# templog3.net
KiCad netlist of a schematic drawn in EAGLE
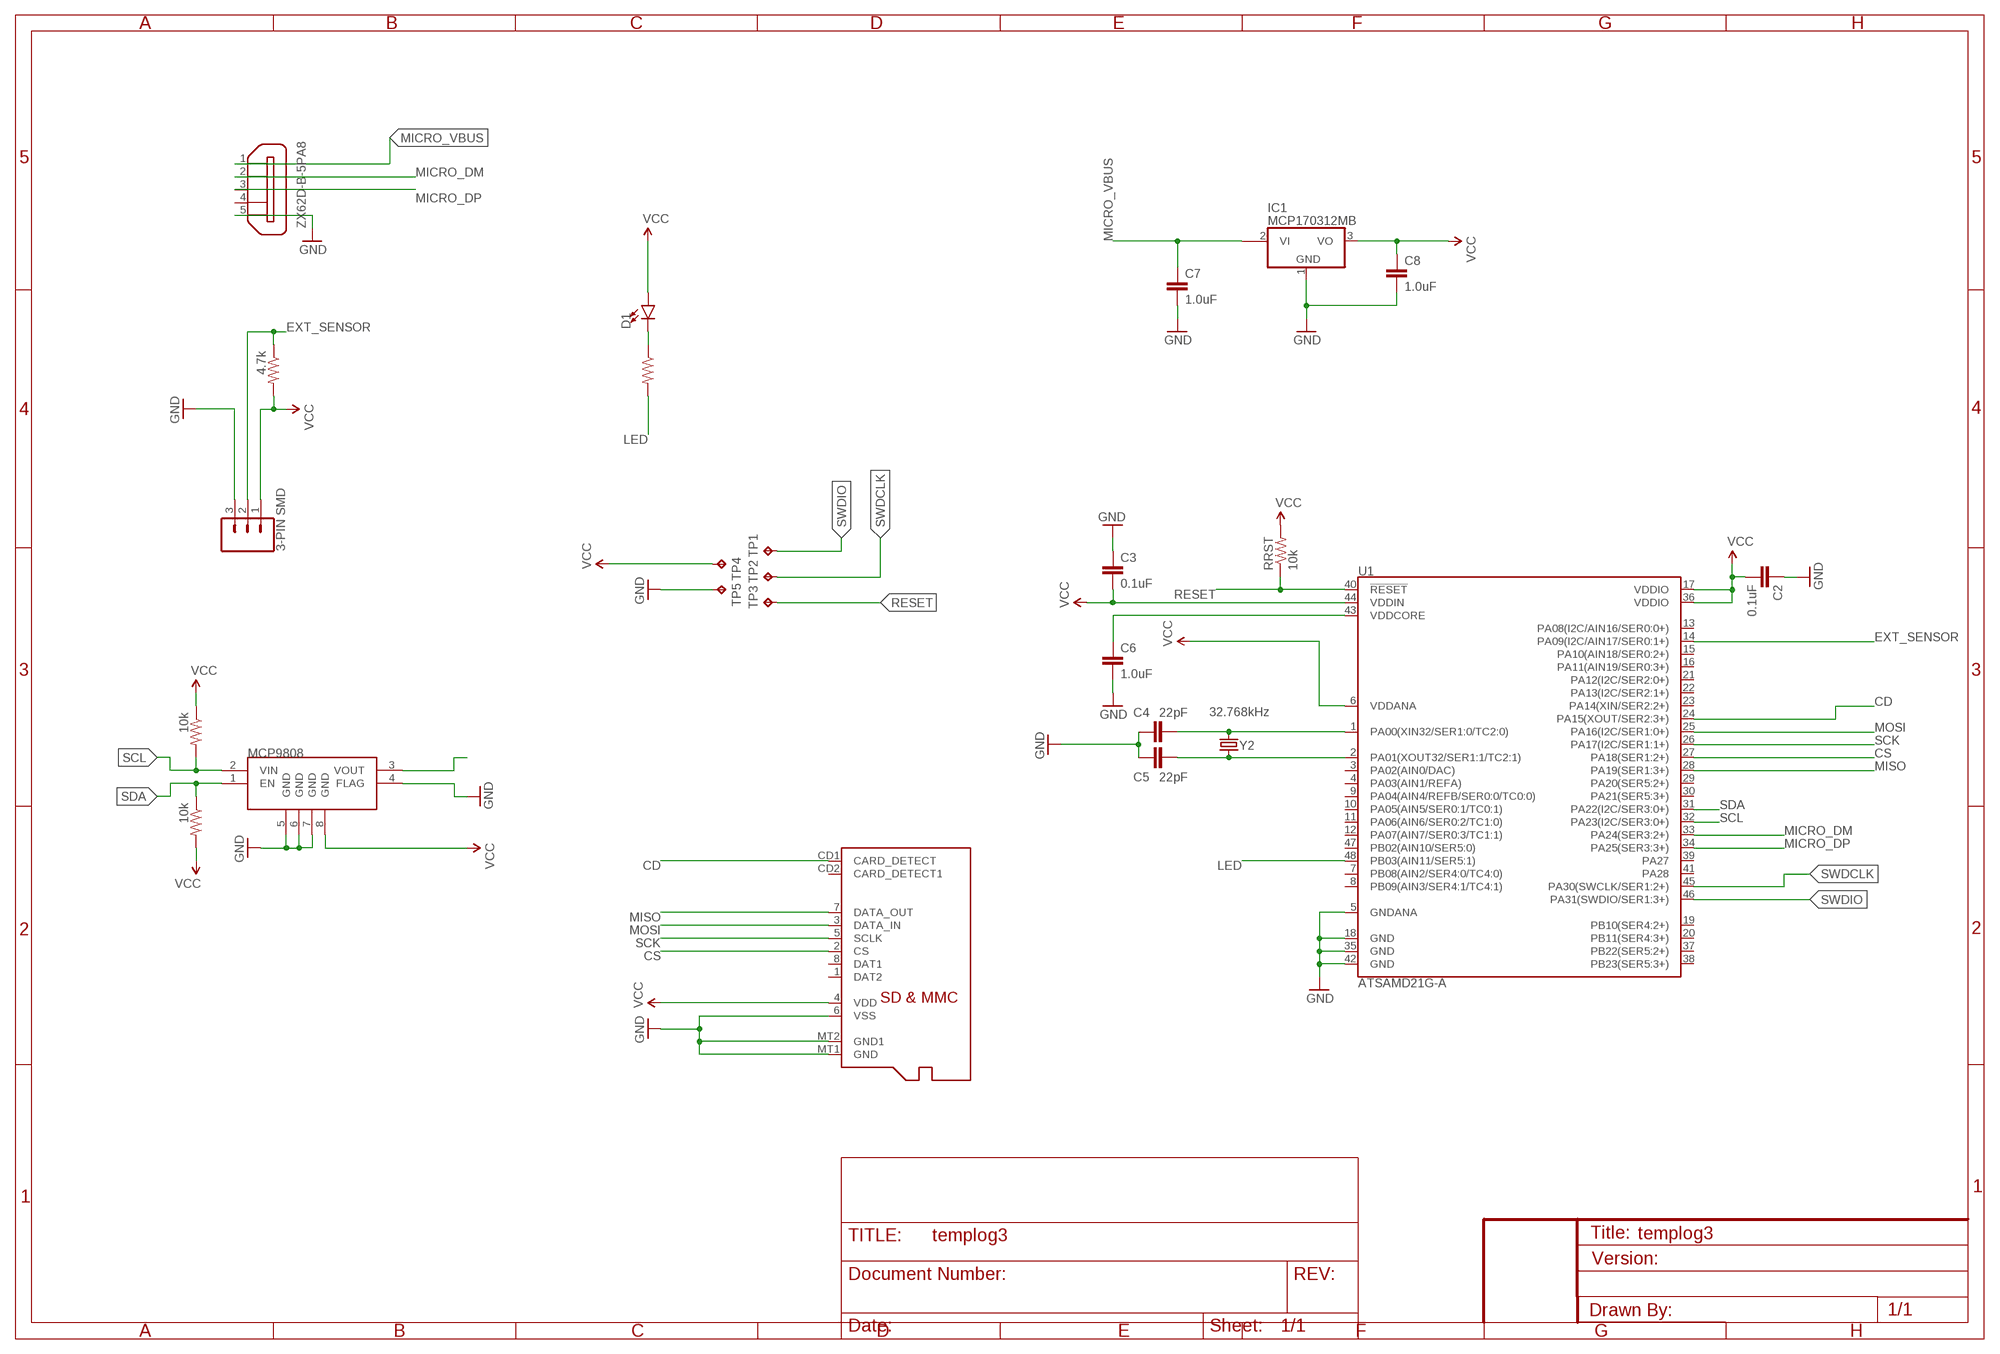
[diagram p0: schematic, sheet 1]

(export (version "E")
  (design (tool "Eeschema 10.0.6"))
  (components
    (comp (ref "C2")
      (value "0.1uF")
      (footprint "eagle-import:0805")
      (libsource (lib "eagle-import") (part "1.0UF-0805-25V-10%"))
    )
    (comp (ref "C3")
      (value "0.1uF")
      (footprint "eagle-import:0805")
      (libsource (lib "eagle-import") (part "1.0UF-0805-25V-10%"))
    )
    (comp (ref "C4")
      (value "22pF")
      (footprint "eagle-import:0805")
      (libsource (lib "eagle-import") (part "CAP0805"))
    )
    (comp (ref "C5")
      (value "22pF")
      (footprint "eagle-import:0805")
      (libsource (lib "eagle-import") (part "CAP0805"))
    )
    (comp (ref "C6")
      (value "1.0uF")
      (footprint "eagle-import:0805")
      (libsource (lib "eagle-import") (part "1.0UF-0805-25V-10%"))
    )
    (comp (ref "C7")
      (value "1.0uF")
      (footprint "eagle-import:0805")
      (libsource (lib "eagle-import") (part "1.0UF-0805-25V-10%"))
    )
    (comp (ref "C8")
      (value "1.0uF")
      (footprint "eagle-import:0805")
      (libsource (lib "eagle-import") (part "1.0UF-0805-25V-10%"))
    )
    (comp (ref "D1")
      (value "LED1206")
      (footprint "eagle-import:LED-1206")
      (libsource (lib "eagle-import") (part "LED1206"))
    )
    (comp (ref "IC1")
      (value "MCP170312MB")
      (footprint "eagle-import:SOT89")
      (libsource (lib "eagle-import") (part "MCP1703MB12"))
    )
    (comp (ref "J2")
      (value "3-PIN SMD")
      (footprint "eagle-import:JST-3-SMD")
      (libsource (lib "eagle-import") (part "CONN_03JST-SMD"))
    )
    (comp (ref "MCP9808")
      (value "V_REG_MIC5216")
      (footprint "eagle-import:MSOP8")
      (libsource (lib "eagle-import") (part "V_REG_MIC5216"))
    )
    (comp (ref "RRST")
      (value "10k")
      (footprint "eagle-import:0805")
      (libsource (lib "eagle-import") (part "RESISTOR0805-RES"))
    )
    (comp (ref "R_I2C_1")
      (value "10k")
      (footprint "eagle-import:0805")
      (libsource (lib "eagle-import") (part "RESISTOR0805-RES"))
    )
    (comp (ref "R_I2C_2")
      (value "10k")
      (footprint "eagle-import:0805")
      (libsource (lib "eagle-import") (part "RESISTOR0805-RES"))
    )
    (comp (ref "R_I2C_3")
      (value "4.7k")
      (footprint "eagle-import:0805")
      (libsource (lib "eagle-import") (part "RESISTOR0805-RES"))
    )
    (comp (ref "R_I2C_4")
      (value "RESISTOR0805-RES")
      (footprint "eagle-import:0805")
      (libsource (lib "eagle-import") (part "RESISTOR0805-RES"))
    )
    (comp (ref "TP1")
      (value "TPB1,27")
      (footprint "eagle-import:B1,27")
      (libsource (lib "eagle-import") (part "TPB1,27"))
    )
    (comp (ref "TP2")
      (value "TPB1,27")
      (footprint "eagle-import:B1,27")
      (libsource (lib "eagle-import") (part "TPB1,27"))
    )
    (comp (ref "TP3")
      (value "TPB1,27")
      (footprint "eagle-import:B1,27")
      (libsource (lib "eagle-import") (part "TPB1,27"))
    )
    (comp (ref "TP4")
      (value "TPB1,27")
      (footprint "eagle-import:B1,27")
      (libsource (lib "eagle-import") (part "TPB1,27"))
    )
    (comp (ref "TP5")
      (value "TPB1,27")
      (footprint "eagle-import:B1,27")
      (libsource (lib "eagle-import") (part "TPB1,27"))
    )
    (comp (ref "U$1")
      (value "MICROSD")
      (footprint "eagle-import:MICROSD")
      (libsource (lib "eagle-import") (part "MICROSD"))
    )
    (comp (ref "U1")
      (value "ATSAMD21G-A")
      (footprint "eagle-import:TQFP-48")
      (libsource (lib "eagle-import") (part "ATSAMD21G-A"))
    )
    (comp (ref "X2")
      (value "ZX62D-B-5PA8")
      (footprint "eagle-import:ZX62D-B-5PA8")
      (fields (field (name "MF") "Hirose"))
      (libsource (lib "eagle-import") (part "ZX62D-B-5PA8"))
    )
    (comp (ref "Y2")
      (value "32.768kHz")
      (footprint "eagle-import:CRYSTAL-SMD-3.2X1.5MM")
      (libsource (lib "eagle-import") (part "CRYSTAL3.2X1.5MM"))
    )
  )
  (nets
    (net (code "1") (name "/CD") (class "Default")
      (node (ref "U$1") (pin "CD1") (pinfunction "CARD_DETECT_CD1") (pintype "passive"))
      (node (ref "U1") (pin "24") (pinfunction "PA15(XOUT/SER2:3+)_24") (pintype "bidirectional"))
    )
    (net (code "2") (name "/CS") (class "Default")
      (node (ref "U$1") (pin "2") (pinfunction "CS_2") (pintype "input"))
      (node (ref "U1") (pin "27") (pinfunction "PA18(SER1:2+)_27") (pintype "bidirectional"))
    )
    (net (code "3") (name "/EXT_SENSOR") (class "Default")
      (node (ref "J2") (pin "2") (pinfunction "2_2") (pintype "passive"))
      (node (ref "R_I2C_3") (pin "1") (pinfunction "1_1") (pintype "passive"))
      (node (ref "U1") (pin "14") (pinfunction "PA09(I2C/AIN17/SER0:1+)_14") (pintype "bidirectional"))
    )
    (net (code "4") (name "/LED") (class "Default")
      (node (ref "R_I2C_4") (pin "2") (pinfunction "2_2") (pintype "passive"))
      (node (ref "U1") (pin "48") (pinfunction "PB03(AIN11/SER5:1)_48") (pintype "bidirectional"))
    )
    (net (code "5") (name "/MICRO_DM") (class "Default")
      (node (ref "U1") (pin "33") (pinfunction "PA24(SER3:2+)_33") (pintype "bidirectional"))
      (node (ref "X2") (pin "2") (pinfunction "2_2") (pintype "passive"))
    )
    (net (code "6") (name "/MICRO_DP") (class "Default")
      (node (ref "U1") (pin "34") (pinfunction "PA25(SER3:3+)_34") (pintype "bidirectional"))
      (node (ref "X2") (pin "3") (pinfunction "3_3") (pintype "passive"))
    )
    (net (code "7") (name "/MISO") (class "Default")
      (node (ref "U$1") (pin "7") (pinfunction "DATA_OUT_7") (pintype "output"))
      (node (ref "U1") (pin "28") (pinfunction "PA19(SER1:3+)_28") (pintype "bidirectional"))
    )
    (net (code "8") (name "/MOSI") (class "Default")
      (node (ref "U$1") (pin "3") (pinfunction "DATA_IN_3") (pintype "input"))
      (node (ref "U1") (pin "25") (pinfunction "PA16(I2C/SER1:0+)_25") (pintype "bidirectional"))
    )
    (net (code "9") (name "/SCK") (class "Default")
      (node (ref "U$1") (pin "5") (pinfunction "SCLK_5") (pintype "input"))
      (node (ref "U1") (pin "26") (pinfunction "PA17(I2C/SER1:1+)_26") (pintype "bidirectional"))
    )
    (net (code "10") (name "GND") (class "Default")
      (node (ref "C2") (pin "1") (pinfunction "1_1") (pintype "passive"))
      (node (ref "C3") (pin "1") (pinfunction "1_1") (pintype "passive"))
      (node (ref "C4") (pin "1") (pinfunction "1_1") (pintype "passive"))
      (node (ref "C5") (pin "1") (pinfunction "1_1") (pintype "passive"))
      (node (ref "C6") (pin "2") (pinfunction "2_2") (pintype "passive"))
      (node (ref "C7") (pin "2") (pinfunction "2_2") (pintype "passive"))
      (node (ref "C8") (pin "2") (pinfunction "2_2") (pintype "passive"))
      (node (ref "IC1") (pin "1") (pinfunction "GND_1") (pintype "passive"))
      (node (ref "J2") (pin "3") (pinfunction "3_3") (pintype "passive"))
      (node (ref "MCP9808") (pin "4") (pinfunction "FLAG_4") (pintype "bidirectional"))
      (node (ref "MCP9808") (pin "5") (pinfunction "GND_5") (pintype "bidirectional"))
      (node (ref "MCP9808") (pin "6") (pinfunction "GND_6") (pintype "bidirectional"))
      (node (ref "MCP9808") (pin "7") (pinfunction "GND_7") (pintype "bidirectional"))
      (node (ref "TP5") (pin "TP") (pinfunction "TP_TP") (pintype "input"))
      (node (ref "U$1") (pin "6") (pinfunction "VSS_6") (pintype "power_in"))
      (node (ref "U$1") (pin "MT1") (pinfunction "GND_MT1") (pintype "power_in"))
      (node (ref "U$1") (pin "MT2") (pinfunction "GND1_MT2") (pintype "power_in"))
      (node (ref "U1") (pin "18") (pinfunction "GND_18") (pintype "bidirectional"))
      (node (ref "U1") (pin "35") (pinfunction "GND_35") (pintype "bidirectional"))
      (node (ref "U1") (pin "42") (pinfunction "GND_42") (pintype "bidirectional"))
      (node (ref "U1") (pin "5") (pinfunction "GNDANA_5") (pintype "bidirectional"))
      (node (ref "X2") (pin "5") (pinfunction "5_5") (pintype "passive"))
    )
    (net (code "11") (name "MICRO_VBUS") (class "Default")
      (node (ref "C7") (pin "1") (pinfunction "1_1") (pintype "passive"))
      (node (ref "IC1") (pin "2@1") (pinfunction "VI1_2@1") (pintype "input"))
      (node (ref "X2") (pin "1") (pinfunction "1_1") (pintype "passive"))
    )
    (net (code "12") (name "Net-(D1-PadC)") (class "Default")
      (node (ref "D1") (pin "C") (pinfunction "C_C") (pintype "passive"))
      (node (ref "R_I2C_4") (pin "1") (pinfunction "1_1") (pintype "passive"))
    )
    (net (code "13") (name "Net-(U1-PA00(XIN32{slash}SER1:0{slash}TC2:0))") (class "Default")
      (node (ref "C4") (pin "2") (pinfunction "2_2") (pintype "passive"))
      (node (ref "U1") (pin "1") (pinfunction "PA00(XIN32/SER1:0/TC2:0)_1") (pintype "bidirectional"))
      (node (ref "Y2") (pin "P$2") (pinfunction "2_P$2") (pintype "passive"))
    )
    (net (code "14") (name "Net-(U1-PA01(XOUT32{slash}SER1:1{slash}TC2:1))") (class "Default")
      (node (ref "C5") (pin "2") (pinfunction "2_2") (pintype "passive"))
      (node (ref "U1") (pin "2") (pinfunction "PA01(XOUT32/SER1:1/TC2:1)_2") (pintype "bidirectional"))
      (node (ref "Y2") (pin "P$1") (pinfunction "1_P$1") (pintype "passive"))
    )
    (net (code "15") (name "Net-(U1-VDDCORE)") (class "Default")
      (node (ref "C6") (pin "1") (pinfunction "1_1") (pintype "passive"))
      (node (ref "U1") (pin "43") (pinfunction "VDDCORE_43") (pintype "bidirectional"))
    )
    (net (code "16") (name "RESET") (class "Default")
      (node (ref "RRST") (pin "1") (pinfunction "1_1") (pintype "passive"))
      (node (ref "TP3") (pin "TP") (pinfunction "TP_TP") (pintype "input"))
      (node (ref "U1") (pin "40") (pinfunction "~{RESET}_40") (pintype "bidirectional"))
    )
    (net (code "17") (name "SCL") (class "Default")
      (node (ref "MCP9808") (pin "2") (pinfunction "VIN_2") (pintype "bidirectional"))
      (node (ref "R_I2C_1") (pin "2") (pinfunction "2_2") (pintype "passive"))
      (node (ref "U1") (pin "32") (pinfunction "PA23(I2C/SER3:0+)_32") (pintype "bidirectional"))
    )
    (net (code "18") (name "SDA") (class "Default")
      (node (ref "MCP9808") (pin "1") (pinfunction "EN_1") (pintype "bidirectional"))
      (node (ref "R_I2C_2") (pin "1") (pinfunction "1_1") (pintype "passive"))
      (node (ref "U1") (pin "31") (pinfunction "PA22(I2C/SER3:0+)_31") (pintype "bidirectional"))
    )
    (net (code "19") (name "SWDCLK") (class "Default")
      (node (ref "TP2") (pin "TP") (pinfunction "TP_TP") (pintype "input"))
      (node (ref "U1") (pin "45") (pinfunction "PA30(SWCLK/SER1:2+)_45") (pintype "bidirectional"))
    )
    (net (code "20") (name "SWDIO") (class "Default")
      (node (ref "TP1") (pin "TP") (pinfunction "TP_TP") (pintype "input"))
      (node (ref "U1") (pin "46") (pinfunction "PA31(SWDIO/SER1:3+)_46") (pintype "bidirectional"))
    )
    (net (code "21") (name "VCC") (class "Default")
      (node (ref "C2") (pin "2") (pinfunction "2_2") (pintype "passive"))
      (node (ref "C3") (pin "2") (pinfunction "2_2") (pintype "passive"))
      (node (ref "C8") (pin "1") (pinfunction "1_1") (pintype "passive"))
      (node (ref "D1") (pin "A") (pinfunction "A_A") (pintype "passive"))
      (node (ref "IC1") (pin "3") (pinfunction "VO_3") (pintype "passive"))
      (node (ref "J2") (pin "1") (pinfunction "1_1") (pintype "passive"))
      (node (ref "MCP9808") (pin "8") (pinfunction "GND_8") (pintype "bidirectional"))
      (node (ref "RRST") (pin "2") (pinfunction "2_2") (pintype "passive"))
      (node (ref "R_I2C_1") (pin "1") (pinfunction "1_1") (pintype "passive"))
      (node (ref "R_I2C_2") (pin "2") (pinfunction "2_2") (pintype "passive"))
      (node (ref "R_I2C_3") (pin "2") (pinfunction "2_2") (pintype "passive"))
      (node (ref "TP4") (pin "TP") (pinfunction "TP_TP") (pintype "input"))
      (node (ref "U$1") (pin "4") (pinfunction "VDD_4") (pintype "power_in"))
      (node (ref "U1") (pin "17") (pinfunction "VDDIO_17") (pintype "bidirectional"))
      (node (ref "U1") (pin "36") (pinfunction "VDDIO_36") (pintype "bidirectional"))
      (node (ref "U1") (pin "44") (pinfunction "VDDIN_44") (pintype "bidirectional"))
      (node (ref "U1") (pin "6") (pinfunction "VDDANA_6") (pintype "bidirectional"))
    )
    (net (code "22") (name "unconnected-(IC1-VI-Pad2)") (class "Default")
      (node (ref "IC1") (pin "2") (pinfunction "VI_2") (pintype "input"))
    )
    (net (code "23") (name "unconnected-(MCP9808-VOUT-Pad3)") (class "Default")
      (node (ref "MCP9808") (pin "3") (pinfunction "VOUT_3") (pintype "bidirectional"))
    )
    (net (code "24") (name "unconnected-(U$1-CARD_DETECT1-PadCD2)") (class "Default")
      (node (ref "U$1") (pin "CD2") (pinfunction "CARD_DETECT1_CD2") (pintype "passive"))
    )
    (net (code "25") (name "unconnected-(U$1-DAT1-Pad8)") (class "Default")
      (node (ref "U$1") (pin "8") (pinfunction "DAT1_8") (pintype "bidirectional"))
    )
    (net (code "26") (name "unconnected-(U$1-DAT2-Pad1)") (class "Default")
      (node (ref "U$1") (pin "1") (pinfunction "DAT2_1") (pintype "bidirectional"))
    )
    (net (code "27") (name "unconnected-(U1-PA02(AIN0{slash}DAC)-Pad3)") (class "Default")
      (node (ref "U1") (pin "3") (pinfunction "PA02(AIN0/DAC)_3") (pintype "bidirectional"))
    )
    (net (code "28") (name "unconnected-(U1-PA03(AIN1{slash}REFA)-Pad4)") (class "Default")
      (node (ref "U1") (pin "4") (pinfunction "PA03(AIN1/REFA)_4") (pintype "bidirectional"))
    )
    (net (code "29") (name "unconnected-(U1-PA04(AIN4{slash}REFB{slash}SER0:0{slash}TC0:0)-Pad9)") (class "Default")
      (node (ref "U1") (pin "9") (pinfunction "PA04(AIN4/REFB/SER0:0/TC0:0)_9") (pintype "bidirectional"))
    )
    (net (code "30") (name "unconnected-(U1-PA05(AIN5{slash}SER0:1{slash}TC0:1)-Pad10)") (class "Default")
      (node (ref "U1") (pin "10") (pinfunction "PA05(AIN5/SER0:1/TC0:1)_10") (pintype "bidirectional"))
    )
    (net (code "31") (name "unconnected-(U1-PA06(AIN6{slash}SER0:2{slash}TC1:0)-Pad11)") (class "Default")
      (node (ref "U1") (pin "11") (pinfunction "PA06(AIN6/SER0:2/TC1:0)_11") (pintype "bidirectional"))
    )
    (net (code "32") (name "unconnected-(U1-PA07(AIN7{slash}SER0:3{slash}TC1:1)-Pad12)") (class "Default")
      (node (ref "U1") (pin "12") (pinfunction "PA07(AIN7/SER0:3/TC1:1)_12") (pintype "bidirectional"))
    )
    (net (code "33") (name "unconnected-(U1-PA08(I2C{slash}AIN16{slash}SER0:0+)-Pad13)") (class "Default")
      (node (ref "U1") (pin "13") (pinfunction "PA08(I2C/AIN16/SER0:0+)_13") (pintype "bidirectional"))
    )
    (net (code "34") (name "unconnected-(U1-PA10(AIN18{slash}SER0:2+)-Pad15)") (class "Default")
      (node (ref "U1") (pin "15") (pinfunction "PA10(AIN18/SER0:2+)_15") (pintype "bidirectional"))
    )
    (net (code "35") (name "unconnected-(U1-PA11(AIN19{slash}SER0:3+)-Pad16)") (class "Default")
      (node (ref "U1") (pin "16") (pinfunction "PA11(AIN19/SER0:3+)_16") (pintype "bidirectional"))
    )
    (net (code "36") (name "unconnected-(U1-PA12(I2C{slash}SER2:0+)-Pad21)") (class "Default")
      (node (ref "U1") (pin "21") (pinfunction "PA12(I2C/SER2:0+)_21") (pintype "bidirectional"))
    )
    (net (code "37") (name "unconnected-(U1-PA13(I2C{slash}SER2:1+)-Pad22)") (class "Default")
      (node (ref "U1") (pin "22") (pinfunction "PA13(I2C/SER2:1+)_22") (pintype "bidirectional"))
    )
    (net (code "38") (name "unconnected-(U1-PA14(XIN{slash}SER2:2+)-Pad23)") (class "Default")
      (node (ref "U1") (pin "23") (pinfunction "PA14(XIN/SER2:2+)_23") (pintype "bidirectional"))
    )
    (net (code "39") (name "unconnected-(U1-PA20(SER5:2+)-Pad29)") (class "Default")
      (node (ref "U1") (pin "29") (pinfunction "PA20(SER5:2+)_29") (pintype "bidirectional"))
    )
    (net (code "40") (name "unconnected-(U1-PA21(SER5:3+)-Pad30)") (class "Default")
      (node (ref "U1") (pin "30") (pinfunction "PA21(SER5:3+)_30") (pintype "bidirectional"))
    )
    (net (code "41") (name "unconnected-(U1-PA27-Pad39)") (class "Default")
      (node (ref "U1") (pin "39") (pinfunction "PA27_39") (pintype "bidirectional"))
    )
    (net (code "42") (name "unconnected-(U1-PA28-Pad41)") (class "Default")
      (node (ref "U1") (pin "41") (pinfunction "PA28_41") (pintype "bidirectional"))
    )
    (net (code "43") (name "unconnected-(U1-PB02(AIN10{slash}SER5:0)-Pad47)") (class "Default")
      (node (ref "U1") (pin "47") (pinfunction "PB02(AIN10/SER5:0)_47") (pintype "bidirectional"))
    )
    (net (code "44") (name "unconnected-(U1-PB08(AIN2{slash}SER4:0{slash}TC4:0)-Pad7)") (class "Default")
      (node (ref "U1") (pin "7") (pinfunction "PB08(AIN2/SER4:0/TC4:0)_7") (pintype "bidirectional"))
    )
    (net (code "45") (name "unconnected-(U1-PB09(AIN3{slash}SER4:1{slash}TC4:1)-Pad8)") (class "Default")
      (node (ref "U1") (pin "8") (pinfunction "PB09(AIN3/SER4:1/TC4:1)_8") (pintype "bidirectional"))
    )
    (net (code "46") (name "unconnected-(U1-PB10(SER4:2+)-Pad19)") (class "Default")
      (node (ref "U1") (pin "19") (pinfunction "PB10(SER4:2+)_19") (pintype "bidirectional"))
    )
    (net (code "47") (name "unconnected-(U1-PB11(SER4:3+)-Pad20)") (class "Default")
      (node (ref "U1") (pin "20") (pinfunction "PB11(SER4:3+)_20") (pintype "bidirectional"))
    )
    (net (code "48") (name "unconnected-(U1-PB22(SER5:2+)-Pad37)") (class "Default")
      (node (ref "U1") (pin "37") (pinfunction "PB22(SER5:2+)_37") (pintype "bidirectional"))
    )
    (net (code "49") (name "unconnected-(U1-PB23(SER5:3+)-Pad38)") (class "Default")
      (node (ref "U1") (pin "38") (pinfunction "PB23(SER5:3+)_38") (pintype "bidirectional"))
    )
    (net (code "50") (name "unconnected-(X2-Pad4)") (class "Default")
      (node (ref "X2") (pin "4") (pinfunction "4_4") (pintype "passive"))
    )
  )
)
